# pca63519_-_Keyboard.net
KiCad netlist of a schematic drawn in Altium Designer
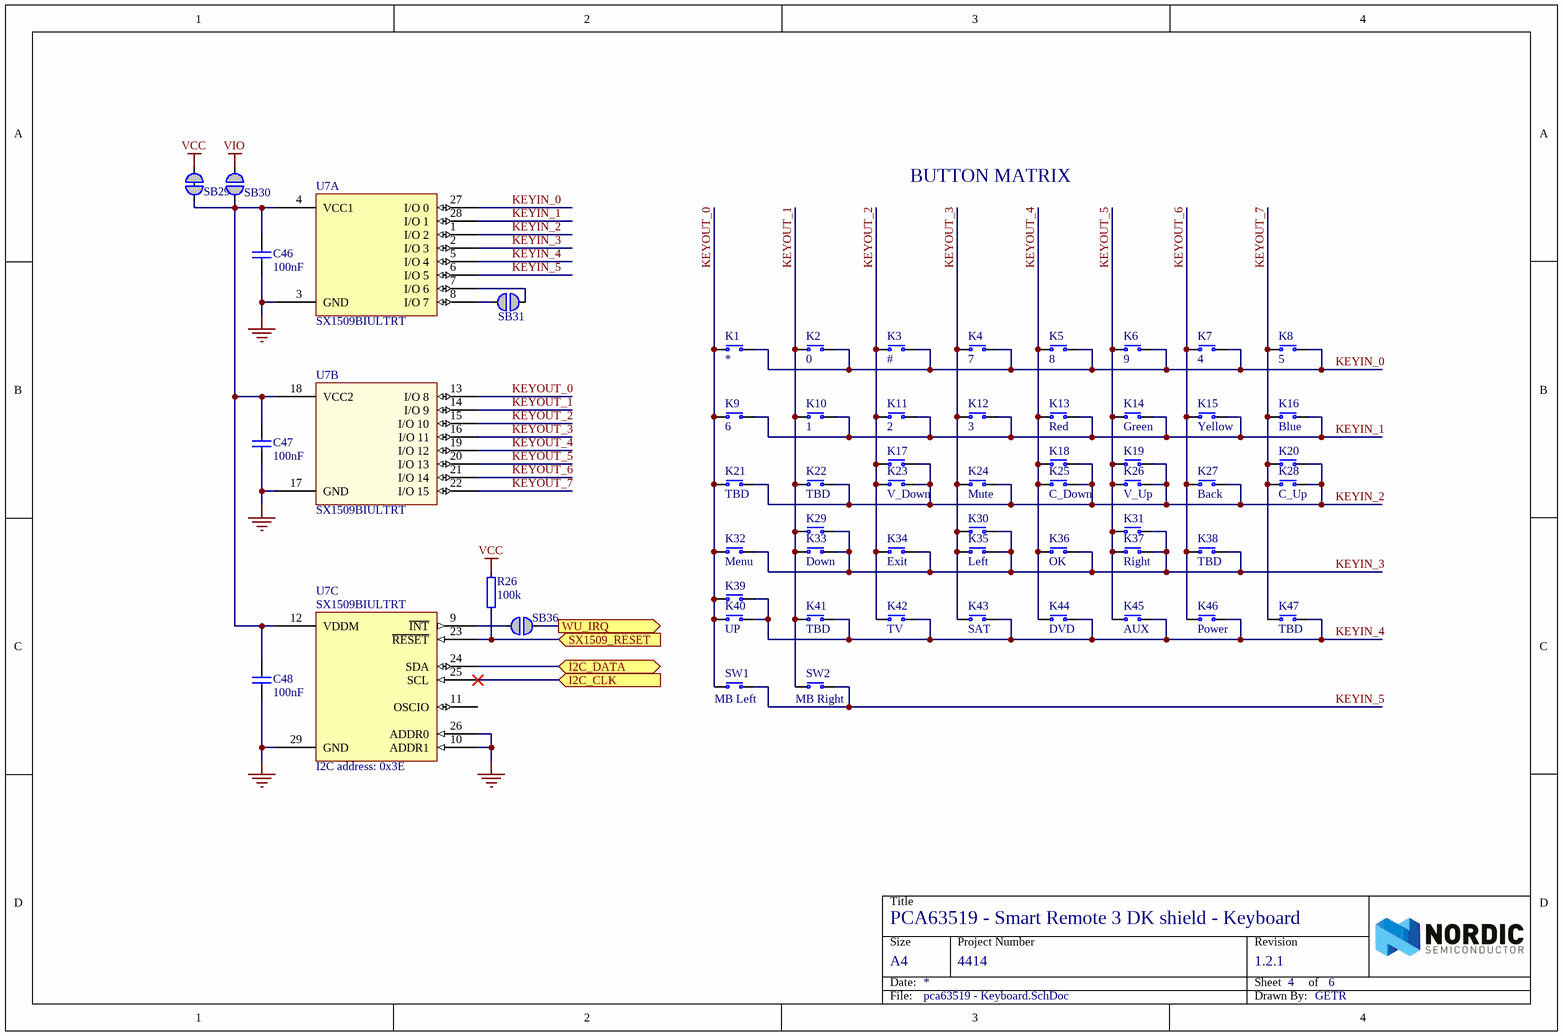
[diagram p0: pca63519 - Keyboard.SchDoc]

(export (version "E")
  (design (tool "Eeschema 10.0.6"))
  (components
    (comp (ref "C46")
      (value "100nF")
      (footprint "CAPC1005X04L")
      (description "Capacitor, X7R, ±10%")
      (fields (field (name "PART NUMBER") "C0402-100n") (field (name "PUBLISHER") "Nordic Semiconductor"))
      (libsource (lib "Nordic Passive DB") (part "CAP"))
    )
    (comp (ref "C47")
      (value "100nF")
      (footprint "CAPC1005X04L")
      (description "Capacitor, X7R, ±10%")
      (fields (field (name "PART NUMBER") "C0402-100n") (field (name "PUBLISHER") "Nordic Semiconductor"))
      (libsource (lib "Nordic Passive DB") (part "CAP"))
    )
    (comp (ref "C48")
      (value "100nF")
      (footprint "CAPC1005X04L")
      (description "Capacitor, X7R, ±10%")
      (fields (field (name "PART NUMBER") "C0402-100n") (field (name "PUBLISHER") "Nordic Semiconductor"))
      (libsource (lib "Nordic Passive DB") (part "CAP"))
    )
    (comp (ref "K1")
      (value "*")
      (footprint "PCB Switch")
      (description "Keyboard matrix switch")
      (fields (field (name "PART NUMBER") "KEY_SWITCH_SR3") (field (name "PUBLISHER") "Nordic Semiconductor"))
      (libsource (lib "Nordic Discrete DB") (part "SW-PCB"))
    )
    (comp (ref "K2")
      (value "0")
      (footprint "PCB Switch")
      (description "Keyboard matrix switch")
      (fields (field (name "PART NUMBER") "KEY_SWITCH_SR3") (field (name "PUBLISHER") "Nordic Semiconductor"))
      (libsource (lib "Nordic Discrete DB") (part "SW-PCB"))
    )
    (comp (ref "K3")
      (value "#")
      (footprint "PCB Switch")
      (description "Keyboard matrix switch")
      (fields (field (name "PART NUMBER") "KEY_SWITCH_SR3") (field (name "PUBLISHER") "Nordic Semiconductor"))
      (libsource (lib "Nordic Discrete DB") (part "SW-PCB"))
    )
    (comp (ref "K4")
      (value "7")
      (footprint "PCB Switch")
      (description "Keyboard matrix switch")
      (fields (field (name "PART NUMBER") "KEY_SWITCH_SR3") (field (name "PUBLISHER") "Nordic Semiconductor"))
      (libsource (lib "Nordic Discrete DB") (part "SW-PCB"))
    )
    (comp (ref "K5")
      (value "8")
      (footprint "PCB Switch")
      (description "Keyboard matrix switch")
      (fields (field (name "PART NUMBER") "KEY_SWITCH_SR3") (field (name "PUBLISHER") "Nordic Semiconductor"))
      (libsource (lib "Nordic Discrete DB") (part "SW-PCB"))
    )
    (comp (ref "K6")
      (value "9")
      (footprint "PCB Switch")
      (description "Keyboard matrix switch")
      (fields (field (name "PART NUMBER") "KEY_SWITCH_SR3") (field (name "PUBLISHER") "Nordic Semiconductor"))
      (libsource (lib "Nordic Discrete DB") (part "SW-PCB"))
    )
    (comp (ref "K7")
      (value "4")
      (footprint "PCB Switch")
      (description "Keyboard matrix switch")
      (fields (field (name "PART NUMBER") "KEY_SWITCH_SR3") (field (name "PUBLISHER") "Nordic Semiconductor"))
      (libsource (lib "Nordic Discrete DB") (part "SW-PCB"))
    )
    (comp (ref "K8")
      (value "5")
      (footprint "PCB Switch")
      (description "Keyboard matrix switch")
      (fields (field (name "PART NUMBER") "KEY_SWITCH_SR3") (field (name "PUBLISHER") "Nordic Semiconductor"))
      (libsource (lib "Nordic Discrete DB") (part "SW-PCB"))
    )
    (comp (ref "K9")
      (value "6")
      (footprint "PCB Switch")
      (description "Keyboard matrix switch")
      (fields (field (name "PART NUMBER") "KEY_SWITCH_SR3") (field (name "PUBLISHER") "Nordic Semiconductor"))
      (libsource (lib "Nordic Discrete DB") (part "SW-PCB"))
    )
    (comp (ref "K10")
      (value "1")
      (footprint "PCB Switch")
      (description "Keyboard matrix switch")
      (fields (field (name "PART NUMBER") "KEY_SWITCH_SR3") (field (name "PUBLISHER") "Nordic Semiconductor"))
      (libsource (lib "Nordic Discrete DB") (part "SW-PCB"))
    )
    (comp (ref "K11")
      (value "2")
      (footprint "PCB Switch")
      (description "Keyboard matrix switch")
      (fields (field (name "PART NUMBER") "KEY_SWITCH_SR3") (field (name "PUBLISHER") "Nordic Semiconductor"))
      (libsource (lib "Nordic Discrete DB") (part "SW-PCB"))
    )
    (comp (ref "K12")
      (value "3")
      (footprint "PCB Switch")
      (description "Keyboard matrix switch")
      (fields (field (name "PART NUMBER") "KEY_SWITCH_SR3") (field (name "PUBLISHER") "Nordic Semiconductor"))
      (libsource (lib "Nordic Discrete DB") (part "SW-PCB"))
    )
    (comp (ref "K13")
      (value "Red")
      (footprint "PCB Switch")
      (description "Keyboard matrix switch")
      (fields (field (name "PART NUMBER") "KEY_SWITCH_SR3") (field (name "PUBLISHER") "Nordic Semiconductor"))
      (libsource (lib "Nordic Discrete DB") (part "SW-PCB"))
    )
    (comp (ref "K14")
      (value "Green")
      (footprint "PCB Switch")
      (description "Keyboard matrix switch")
      (fields (field (name "PART NUMBER") "KEY_SWITCH_SR3") (field (name "PUBLISHER") "Nordic Semiconductor"))
      (libsource (lib "Nordic Discrete DB") (part "SW-PCB"))
    )
    (comp (ref "K15")
      (value "Yellow")
      (footprint "PCB Switch")
      (description "Keyboard matrix switch")
      (fields (field (name "PART NUMBER") "KEY_SWITCH_SR3") (field (name "PUBLISHER") "Nordic Semiconductor"))
      (libsource (lib "Nordic Discrete DB") (part "SW-PCB"))
    )
    (comp (ref "K16")
      (value "Blue")
      (footprint "PCB Switch")
      (description "Keyboard matrix switch")
      (fields (field (name "PART NUMBER") "KEY_SWITCH_SR3") (field (name "PUBLISHER") "Nordic Semiconductor"))
      (libsource (lib "Nordic Discrete DB") (part "SW-PCB"))
    )
    (comp (ref "K17")
      (value "PCB SW")
      (footprint "PCB Switch")
      (description "Keyboard matrix switch")
      (fields (field (name "PART NUMBER") "KEY_SWITCH_SR3") (field (name "PUBLISHER") "Nordic Semiconductor"))
      (libsource (lib "Nordic Discrete DB") (part "SW-PCB"))
    )
    (comp (ref "K18")
      (value "PCB SW")
      (footprint "PCB Switch")
      (description "Keyboard matrix switch")
      (fields (field (name "PART NUMBER") "KEY_SWITCH_SR3") (field (name "PUBLISHER") "Nordic Semiconductor"))
      (libsource (lib "Nordic Discrete DB") (part "SW-PCB"))
    )
    (comp (ref "K19")
      (value "PCB SW")
      (footprint "PCB Switch")
      (description "Keyboard matrix switch")
      (fields (field (name "PART NUMBER") "KEY_SWITCH_SR3") (field (name "PUBLISHER") "Nordic Semiconductor"))
      (libsource (lib "Nordic Discrete DB") (part "SW-PCB"))
    )
    (comp (ref "K20")
      (value "PCB SW")
      (footprint "PCB Switch")
      (description "Keyboard matrix switch")
      (fields (field (name "PART NUMBER") "KEY_SWITCH_SR3") (field (name "PUBLISHER") "Nordic Semiconductor"))
      (libsource (lib "Nordic Discrete DB") (part "SW-PCB"))
    )
    (comp (ref "K21")
      (value "TBD")
      (footprint "PCB Switch")
      (description "Keyboard matrix switch")
      (fields (field (name "PART NUMBER") "KEY_SWITCH_SR3") (field (name "PUBLISHER") "Nordic Semiconductor"))
      (libsource (lib "Nordic Discrete DB") (part "SW-PCB"))
    )
    (comp (ref "K22")
      (value "TBD")
      (footprint "PCB Switch")
      (description "Keyboard matrix switch")
      (fields (field (name "PART NUMBER") "KEY_SWITCH_SR3") (field (name "PUBLISHER") "Nordic Semiconductor"))
      (libsource (lib "Nordic Discrete DB") (part "SW-PCB"))
    )
    (comp (ref "K23")
      (value "V_Down")
      (footprint "PCB Switch")
      (description "Keyboard matrix switch")
      (fields (field (name "PART NUMBER") "KEY_SWITCH_SR3") (field (name "PUBLISHER") "Nordic Semiconductor"))
      (libsource (lib "Nordic Discrete DB") (part "SW-PCB"))
    )
    (comp (ref "K24")
      (value "Mute")
      (footprint "PCB Switch")
      (description "Keyboard matrix switch")
      (fields (field (name "PART NUMBER") "KEY_SWITCH_SR3") (field (name "PUBLISHER") "Nordic Semiconductor"))
      (libsource (lib "Nordic Discrete DB") (part "SW-PCB"))
    )
    (comp (ref "K25")
      (value "C_Down")
      (footprint "PCB Switch")
      (description "Keyboard matrix switch")
      (fields (field (name "PART NUMBER") "KEY_SWITCH_SR3") (field (name "PUBLISHER") "Nordic Semiconductor"))
      (libsource (lib "Nordic Discrete DB") (part "SW-PCB"))
    )
    (comp (ref "K26")
      (value "V_Up")
      (footprint "PCB Switch")
      (description "Keyboard matrix switch")
      (fields (field (name "PART NUMBER") "KEY_SWITCH_SR3") (field (name "PUBLISHER") "Nordic Semiconductor"))
      (libsource (lib "Nordic Discrete DB") (part "SW-PCB"))
    )
    (comp (ref "K27")
      (value "Back")
      (footprint "PCB Switch")
      (description "Keyboard matrix switch")
      (fields (field (name "PART NUMBER") "KEY_SWITCH_SR3") (field (name "PUBLISHER") "Nordic Semiconductor"))
      (libsource (lib "Nordic Discrete DB") (part "SW-PCB"))
    )
    (comp (ref "K28")
      (value "C_Up")
      (footprint "PCB Switch")
      (description "Keyboard matrix switch")
      (fields (field (name "PART NUMBER") "KEY_SWITCH_SR3") (field (name "PUBLISHER") "Nordic Semiconductor"))
      (libsource (lib "Nordic Discrete DB") (part "SW-PCB"))
    )
    (comp (ref "K29")
      (value "PCB SW")
      (footprint "PCB Switch")
      (description "Keyboard matrix switch")
      (fields (field (name "PART NUMBER") "KEY_SWITCH_SR3") (field (name "PUBLISHER") "Nordic Semiconductor"))
      (libsource (lib "Nordic Discrete DB") (part "SW-PCB"))
    )
    (comp (ref "K30")
      (value "PCB SW")
      (footprint "PCB Switch")
      (description "Keyboard matrix switch")
      (fields (field (name "PART NUMBER") "KEY_SWITCH_SR3") (field (name "PUBLISHER") "Nordic Semiconductor"))
      (libsource (lib "Nordic Discrete DB") (part "SW-PCB"))
    )
    (comp (ref "K31")
      (value "PCB SW")
      (footprint "PCB Switch")
      (description "Keyboard matrix switch")
      (fields (field (name "PART NUMBER") "KEY_SWITCH_SR3") (field (name "PUBLISHER") "Nordic Semiconductor"))
      (libsource (lib "Nordic Discrete DB") (part "SW-PCB"))
    )
    (comp (ref "K32")
      (value "Menu")
      (footprint "PCB Switch")
      (description "Keyboard matrix switch")
      (fields (field (name "PART NUMBER") "KEY_SWITCH_SR3") (field (name "PUBLISHER") "Nordic Semiconductor"))
      (libsource (lib "Nordic Discrete DB") (part "SW-PCB"))
    )
    (comp (ref "K33")
      (value "Down")
      (footprint "PCB Switch")
      (description "Keyboard matrix switch")
      (fields (field (name "PART NUMBER") "KEY_SWITCH_SR3") (field (name "PUBLISHER") "Nordic Semiconductor"))
      (libsource (lib "Nordic Discrete DB") (part "SW-PCB"))
    )
    (comp (ref "K34")
      (value "Exit")
      (footprint "PCB Switch")
      (description "Keyboard matrix switch")
      (fields (field (name "PART NUMBER") "KEY_SWITCH_SR3") (field (name "PUBLISHER") "Nordic Semiconductor"))
      (libsource (lib "Nordic Discrete DB") (part "SW-PCB"))
    )
    (comp (ref "K35")
      (value "Left")
      (footprint "PCB Switch")
      (description "Keyboard matrix switch")
      (fields (field (name "PART NUMBER") "KEY_SWITCH_SR3") (field (name "PUBLISHER") "Nordic Semiconductor"))
      (libsource (lib "Nordic Discrete DB") (part "SW-PCB"))
    )
    (comp (ref "K36")
      (value "OK")
      (footprint "PCB Switch")
      (description "Keyboard matrix switch")
      (fields (field (name "PART NUMBER") "KEY_SWITCH_SR3") (field (name "PUBLISHER") "Nordic Semiconductor"))
      (libsource (lib "Nordic Discrete DB") (part "SW-PCB"))
    )
    (comp (ref "K37")
      (value "Right")
      (footprint "PCB Switch")
      (description "Keyboard matrix switch")
      (fields (field (name "PART NUMBER") "KEY_SWITCH_SR3") (field (name "PUBLISHER") "Nordic Semiconductor"))
      (libsource (lib "Nordic Discrete DB") (part "SW-PCB"))
    )
    (comp (ref "K38")
      (value "TBD")
      (footprint "PCB Switch")
      (description "Keyboard matrix switch")
      (fields (field (name "PART NUMBER") "KEY_SWITCH_SR3") (field (name "PUBLISHER") "Nordic Semiconductor"))
      (libsource (lib "Nordic Discrete DB") (part "SW-PCB"))
    )
    (comp (ref "K39")
      (value "PCB SW")
      (footprint "PCB Switch")
      (description "Keyboard matrix switch")
      (fields (field (name "PART NUMBER") "KEY_SWITCH_SR3") (field (name "PUBLISHER") "Nordic Semiconductor"))
      (libsource (lib "Nordic Discrete DB") (part "SW-PCB"))
    )
    (comp (ref "K40")
      (value "UP")
      (footprint "PCB Switch")
      (description "Keyboard matrix switch")
      (fields (field (name "PART NUMBER") "KEY_SWITCH_SR3") (field (name "PUBLISHER") "Nordic Semiconductor"))
      (libsource (lib "Nordic Discrete DB") (part "SW-PCB"))
    )
    (comp (ref "K41")
      (value "TBD")
      (footprint "PCB Switch")
      (description "Keyboard matrix switch")
      (fields (field (name "PART NUMBER") "KEY_SWITCH_SR3") (field (name "PUBLISHER") "Nordic Semiconductor"))
      (libsource (lib "Nordic Discrete DB") (part "SW-PCB"))
    )
    (comp (ref "K42")
      (value "TV")
      (footprint "PCB Switch")
      (description "Keyboard matrix switch")
      (fields (field (name "PART NUMBER") "KEY_SWITCH_SR3") (field (name "PUBLISHER") "Nordic Semiconductor"))
      (libsource (lib "Nordic Discrete DB") (part "SW-PCB"))
    )
    (comp (ref "K43")
      (value "SAT")
      (footprint "PCB Switch")
      (description "Keyboard matrix switch")
      (fields (field (name "PART NUMBER") "KEY_SWITCH_SR3") (field (name "PUBLISHER") "Nordic Semiconductor"))
      (libsource (lib "Nordic Discrete DB") (part "SW-PCB"))
    )
    (comp (ref "K44")
      (value "DVD")
      (footprint "PCB Switch")
      (description "Keyboard matrix switch")
      (fields (field (name "PART NUMBER") "KEY_SWITCH_SR3") (field (name "PUBLISHER") "Nordic Semiconductor"))
      (libsource (lib "Nordic Discrete DB") (part "SW-PCB"))
    )
    (comp (ref "K45")
      (value "AUX")
      (footprint "PCB Switch")
      (description "Keyboard matrix switch")
      (fields (field (name "PART NUMBER") "KEY_SWITCH_SR3") (field (name "PUBLISHER") "Nordic Semiconductor"))
      (libsource (lib "Nordic Discrete DB") (part "SW-PCB"))
    )
    (comp (ref "K46")
      (value "Power")
      (footprint "PCB Switch")
      (description "Keyboard matrix switch")
      (fields (field (name "PART NUMBER") "KEY_SWITCH_SR3") (field (name "PUBLISHER") "Nordic Semiconductor"))
      (libsource (lib "Nordic Discrete DB") (part "SW-PCB"))
    )
    (comp (ref "K47")
      (value "TBD")
      (footprint "PCB Switch")
      (description "Keyboard matrix switch")
      (fields (field (name "PART NUMBER") "KEY_SWITCH_SR3") (field (name "PUBLISHER") "Nordic Semiconductor"))
      (libsource (lib "Nordic Discrete DB") (part "SW-PCB"))
    )
    (comp (ref "R26")
      (value "100k")
      (footprint "RESC1005X04L")
      (description "Resistor, ±1%, 0.063W")
      (fields (field (name "PART NUMBER") "R0402-100k") (field (name "PUBLISHER") "Nordic Semiconductor"))
      (libsource (lib "Nordic Passive DB") (part "RES_1"))
    )
    (comp (ref "SB29")
      (value "Solderbridge")
      (footprint "Solderbridge_SHORTED_0.4")
      (description "Shorted Solderbridge")
      (fields
        (field (name "PART NUMBER") "Solderbridge Shorted 0.4mm")
        (field (name "PUBLISHER") "Nordic Semiconductor")
      )
      (libsource (lib "Nordic Passive DB") (part "SOLDERBRIDGE_SHORTED"))
    )
    (comp (ref "SB30")
      (value "Solderbridge")
      (footprint "Solderbridge_0.4")
      (fields
        (field (name "PART NUMBER") "Solderbridge 0.4mm")
        (field (name "PUBLISHER") "Nordic Semiconductor")
      )
      (libsource (lib "Nordic Passive DB") (part "SOLDERBRIDGE"))
    )
    (comp (ref "SB31")
      (value "Solderbridge")
      (footprint "Solderbridge_0.4")
      (fields
        (field (name "PART NUMBER") "Solderbridge 0.4mm")
        (field (name "PUBLISHER") "Nordic Semiconductor")
      )
      (libsource (lib "Nordic Passive DB") (part "SOLDERBRIDGE"))
    )
    (comp (ref "SB36")
      (value "Solderbridge")
      (footprint "Solderbridge_0.4")
      (fields
        (field (name "PART NUMBER") "Solderbridge 0.4mm")
        (field (name "PUBLISHER") "Nordic Semiconductor")
      )
      (libsource (lib "Nordic Passive DB") (part "SOLDERBRIDGE"))
    )
    (comp (ref "SW1")
      (value "MB Left")
      (footprint "ALPS_SKHUxxx010_WO_GND")
      (description "ALPS - SKHUALE010 - Tactile Switch, SPNO, SMD, 6.5x6.2x2.5mm")
      (fields
        (field (name "PART NUMBER") "ALPS_SKHUALE010")
        (field (name "MANUFACTURER") "Alps")
        (field (name "PUBLISHER") "Nordic Semiconductor")
      )
      (libsource (lib "Nordic Discrete DB") (part "SW-PB"))
    )
    (comp (ref "SW2")
      (value "MB Right")
      (footprint "ALPS_SKHUxxx010_WO_GND")
      (description "ALPS - SKHUALE010 - Tactile Switch, SPNO, SMD, 6.5x6.2x2.5mm")
      (fields
        (field (name "PART NUMBER") "ALPS_SKHUALE010")
        (field (name "MANUFACTURER") "Alps")
        (field (name "PUBLISHER") "Nordic Semiconductor")
      )
      (libsource (lib "Nordic Discrete DB") (part "SW-PB"))
    )
    (comp (ref "U7")
      (value "SX1509BIULTRT")
      (footprint "QFN40P400X400X60_HS-29N")
      (description "IC GPIO EXPANDER I2C 16CH 28QFN")
      (fields
        (field (name "MANUFACTURER") "Semtech Corporation")
        (field (name "PUBLISHER") "Nordic Semiconductor")
      )
      (libsource (lib "Nordic Active DB") (part "SX1509"))
    )
  )
  (nets
    (net (code "1") (name "/I2C_CLK") (class "Default")
      (node (ref "U7") (pin "25") (pinfunction "SCL_25") (pintype "input+no_connect"))
    )
    (net (code "2") (name "/I2C_DATA") (class "Default")
      (node (ref "U7") (pin "24") (pinfunction "SDA_24") (pintype "bidirectional"))
    )
    (net (code "3") (name "/KEYIN_0") (class "Default")
      (node (ref "K1") (pin "1") (pinfunction "N.O_1") (pintype "passive"))
      (node (ref "K2") (pin "1") (pinfunction "N.O_1") (pintype "passive"))
      (node (ref "K3") (pin "1") (pinfunction "N.O_1") (pintype "passive"))
      (node (ref "K4") (pin "1") (pinfunction "N.O_1") (pintype "passive"))
      (node (ref "K5") (pin "1") (pinfunction "N.O_1") (pintype "passive"))
      (node (ref "K6") (pin "1") (pinfunction "N.O_1") (pintype "passive"))
      (node (ref "K7") (pin "1") (pinfunction "N.O_1") (pintype "passive"))
      (node (ref "K8") (pin "1") (pinfunction "N.O_1") (pintype "passive"))
      (node (ref "U7") (pin "27") (pinfunction "I/O_0_27") (pintype "bidirectional"))
    )
    (net (code "4") (name "/KEYIN_1") (class "Default")
      (node (ref "K10") (pin "1") (pinfunction "N.O_1") (pintype "passive"))
      (node (ref "K11") (pin "1") (pinfunction "N.O_1") (pintype "passive"))
      (node (ref "K12") (pin "1") (pinfunction "N.O_1") (pintype "passive"))
      (node (ref "K13") (pin "1") (pinfunction "N.O_1") (pintype "passive"))
      (node (ref "K14") (pin "1") (pinfunction "N.O_1") (pintype "passive"))
      (node (ref "K15") (pin "1") (pinfunction "N.O_1") (pintype "passive"))
      (node (ref "K16") (pin "1") (pinfunction "N.O_1") (pintype "passive"))
      (node (ref "K9") (pin "1") (pinfunction "N.O_1") (pintype "passive"))
      (node (ref "U7") (pin "28") (pinfunction "I/O_1_28") (pintype "bidirectional"))
    )
    (net (code "5") (name "/KEYIN_2") (class "Default")
      (node (ref "K17") (pin "1") (pinfunction "N.O_1") (pintype "passive"))
      (node (ref "K18") (pin "1") (pinfunction "N.O_1") (pintype "passive"))
      (node (ref "K19") (pin "1") (pinfunction "N.O_1") (pintype "passive"))
      (node (ref "K20") (pin "1") (pinfunction "N.O_1") (pintype "passive"))
      (node (ref "K21") (pin "1") (pinfunction "N.O_1") (pintype "passive"))
      (node (ref "K22") (pin "1") (pinfunction "N.O_1") (pintype "passive"))
      (node (ref "K23") (pin "1") (pinfunction "N.O_1") (pintype "passive"))
      (node (ref "K24") (pin "1") (pinfunction "N.O_1") (pintype "passive"))
      (node (ref "K25") (pin "1") (pinfunction "N.O_1") (pintype "passive"))
      (node (ref "K26") (pin "1") (pinfunction "N.O_1") (pintype "passive"))
      (node (ref "K27") (pin "1") (pinfunction "N.O_1") (pintype "passive"))
      (node (ref "K28") (pin "1") (pinfunction "N.O_1") (pintype "passive"))
      (node (ref "U7") (pin "1") (pinfunction "I/O_2_1") (pintype "bidirectional"))
    )
    (net (code "6") (name "/KEYIN_3") (class "Default")
      (node (ref "K29") (pin "1") (pinfunction "N.O_1") (pintype "passive"))
      (node (ref "K30") (pin "1") (pinfunction "N.O_1") (pintype "passive"))
      (node (ref "K31") (pin "1") (pinfunction "N.O_1") (pintype "passive"))
      (node (ref "K32") (pin "1") (pinfunction "N.O_1") (pintype "passive"))
      (node (ref "K33") (pin "1") (pinfunction "N.O_1") (pintype "passive"))
      (node (ref "K34") (pin "1") (pinfunction "N.O_1") (pintype "passive"))
      (node (ref "K35") (pin "1") (pinfunction "N.O_1") (pintype "passive"))
      (node (ref "K36") (pin "1") (pinfunction "N.O_1") (pintype "passive"))
      (node (ref "K37") (pin "1") (pinfunction "N.O_1") (pintype "passive"))
      (node (ref "K38") (pin "1") (pinfunction "N.O_1") (pintype "passive"))
      (node (ref "U7") (pin "2") (pinfunction "I/O_3_2") (pintype "bidirectional"))
    )
    (net (code "7") (name "/KEYIN_4") (class "Default")
      (node (ref "K39") (pin "1") (pinfunction "N.O_1") (pintype "passive"))
      (node (ref "K40") (pin "1") (pinfunction "N.O_1") (pintype "passive"))
      (node (ref "K41") (pin "1") (pinfunction "N.O_1") (pintype "passive"))
      (node (ref "K42") (pin "1") (pinfunction "N.O_1") (pintype "passive"))
      (node (ref "K43") (pin "1") (pinfunction "N.O_1") (pintype "passive"))
      (node (ref "K44") (pin "1") (pinfunction "N.O_1") (pintype "passive"))
      (node (ref "K45") (pin "1") (pinfunction "N.O_1") (pintype "passive"))
      (node (ref "K46") (pin "1") (pinfunction "N.O_1") (pintype "passive"))
      (node (ref "K47") (pin "1") (pinfunction "N.O_1") (pintype "passive"))
      (node (ref "U7") (pin "5") (pinfunction "I/O_4_5") (pintype "bidirectional"))
    )
    (net (code "8") (name "/KEYIN_5") (class "Default")
      (node (ref "SW1") (pin "1") (pinfunction "N.O_1") (pintype "passive"))
      (node (ref "SW2") (pin "1") (pinfunction "N.O_1") (pintype "passive"))
      (node (ref "U7") (pin "6") (pinfunction "I/O_5_6") (pintype "bidirectional"))
    )
    (net (code "9") (name "/KEYOUT_0") (class "Default")
      (node (ref "K1") (pin "2") (pinfunction "COM_2") (pintype "passive"))
      (node (ref "K21") (pin "2") (pinfunction "COM_2") (pintype "passive"))
      (node (ref "K32") (pin "2") (pinfunction "COM_2") (pintype "passive"))
      (node (ref "K39") (pin "2") (pinfunction "COM_2") (pintype "passive"))
      (node (ref "K40") (pin "2") (pinfunction "COM_2") (pintype "passive"))
      (node (ref "K9") (pin "2") (pinfunction "COM_2") (pintype "passive"))
      (node (ref "SW1") (pin "2") (pinfunction "COM_2") (pintype "passive"))
      (node (ref "U7") (pin "13") (pinfunction "I/O_8_13") (pintype "bidirectional"))
    )
    (net (code "10") (name "/KEYOUT_1") (class "Default")
      (node (ref "K10") (pin "2") (pinfunction "COM_2") (pintype "passive"))
      (node (ref "K2") (pin "2") (pinfunction "COM_2") (pintype "passive"))
      (node (ref "K22") (pin "2") (pinfunction "COM_2") (pintype "passive"))
      (node (ref "K29") (pin "2") (pinfunction "COM_2") (pintype "passive"))
      (node (ref "K33") (pin "2") (pinfunction "COM_2") (pintype "passive"))
      (node (ref "K41") (pin "2") (pinfunction "COM_2") (pintype "passive"))
      (node (ref "SW2") (pin "2") (pinfunction "COM_2") (pintype "passive"))
      (node (ref "U7") (pin "14") (pinfunction "I/O_9_14") (pintype "bidirectional"))
    )
    (net (code "11") (name "/KEYOUT_2") (class "Default")
      (node (ref "K11") (pin "2") (pinfunction "COM_2") (pintype "passive"))
      (node (ref "K17") (pin "2") (pinfunction "COM_2") (pintype "passive"))
      (node (ref "K23") (pin "2") (pinfunction "COM_2") (pintype "passive"))
      (node (ref "K3") (pin "2") (pinfunction "COM_2") (pintype "passive"))
      (node (ref "K34") (pin "2") (pinfunction "COM_2") (pintype "passive"))
      (node (ref "K42") (pin "2") (pinfunction "COM_2") (pintype "passive"))
      (node (ref "U7") (pin "15") (pinfunction "I/O_10_15") (pintype "bidirectional"))
    )
    (net (code "12") (name "/KEYOUT_3") (class "Default")
      (node (ref "K12") (pin "2") (pinfunction "COM_2") (pintype "passive"))
      (node (ref "K24") (pin "2") (pinfunction "COM_2") (pintype "passive"))
      (node (ref "K30") (pin "2") (pinfunction "COM_2") (pintype "passive"))
      (node (ref "K35") (pin "2") (pinfunction "COM_2") (pintype "passive"))
      (node (ref "K4") (pin "2") (pinfunction "COM_2") (pintype "passive"))
      (node (ref "K43") (pin "2") (pinfunction "COM_2") (pintype "passive"))
      (node (ref "U7") (pin "16") (pinfunction "I/O_11_16") (pintype "bidirectional"))
    )
    (net (code "13") (name "/KEYOUT_4") (class "Default")
      (node (ref "K13") (pin "2") (pinfunction "COM_2") (pintype "passive"))
      (node (ref "K18") (pin "2") (pinfunction "COM_2") (pintype "passive"))
      (node (ref "K25") (pin "2") (pinfunction "COM_2") (pintype "passive"))
      (node (ref "K36") (pin "2") (pinfunction "COM_2") (pintype "passive"))
      (node (ref "K44") (pin "2") (pinfunction "COM_2") (pintype "passive"))
      (node (ref "K5") (pin "2") (pinfunction "COM_2") (pintype "passive"))
      (node (ref "U7") (pin "19") (pinfunction "I/O_12_19") (pintype "bidirectional"))
    )
    (net (code "14") (name "/KEYOUT_5") (class "Default")
      (node (ref "K14") (pin "2") (pinfunction "COM_2") (pintype "passive"))
      (node (ref "K19") (pin "2") (pinfunction "COM_2") (pintype "passive"))
      (node (ref "K26") (pin "2") (pinfunction "COM_2") (pintype "passive"))
      (node (ref "K31") (pin "2") (pinfunction "COM_2") (pintype "passive"))
      (node (ref "K37") (pin "2") (pinfunction "COM_2") (pintype "passive"))
      (node (ref "K45") (pin "2") (pinfunction "COM_2") (pintype "passive"))
      (node (ref "K6") (pin "2") (pinfunction "COM_2") (pintype "passive"))
      (node (ref "U7") (pin "20") (pinfunction "I/O_13_20") (pintype "bidirectional"))
    )
    (net (code "15") (name "/KEYOUT_6") (class "Default")
      (node (ref "K15") (pin "2") (pinfunction "COM_2") (pintype "passive"))
      (node (ref "K27") (pin "2") (pinfunction "COM_2") (pintype "passive"))
      (node (ref "K38") (pin "2") (pinfunction "COM_2") (pintype "passive"))
      (node (ref "K46") (pin "2") (pinfunction "COM_2") (pintype "passive"))
      (node (ref "K7") (pin "2") (pinfunction "COM_2") (pintype "passive"))
      (node (ref "U7") (pin "21") (pinfunction "I/O_14_21") (pintype "bidirectional"))
    )
    (net (code "16") (name "/KEYOUT_7") (class "Default")
      (node (ref "K16") (pin "2") (pinfunction "COM_2") (pintype "passive"))
      (node (ref "K20") (pin "2") (pinfunction "COM_2") (pintype "passive"))
      (node (ref "K28") (pin "2") (pinfunction "COM_2") (pintype "passive"))
      (node (ref "K47") (pin "2") (pinfunction "COM_2") (pintype "passive"))
      (node (ref "K8") (pin "2") (pinfunction "COM_2") (pintype "passive"))
      (node (ref "U7") (pin "22") (pinfunction "I/O_15_22") (pintype "bidirectional"))
    )
    (net (code "17") (name "/SX1509_RESET") (class "Default")
      (node (ref "R26") (pin "1") (pinfunction "1_1") (pintype "passive"))
      (node (ref "U7") (pin "23") (pinfunction "~{RESET}_23") (pintype "input"))
    )
    (net (code "18") (name "/WU_IRQ") (class "Default")
      (node (ref "SB36") (pin "1") (pinfunction "0_1") (pintype "passive"))
    )
    (net (code "19") (name "GND") (class "Default")
      (node (ref "C46") (pin "1") (pinfunction "1_1") (pintype "passive"))
      (node (ref "C47") (pin "1") (pinfunction "1_1") (pintype "passive"))
      (node (ref "C48") (pin "1") (pinfunction "1_1") (pintype "passive"))
      (node (ref "U7") (pin "10") (pinfunction "ADDR1_10") (pintype "input"))
      (node (ref "U7") (pin "17") (pinfunction "GND_17") (pintype "power_in"))
      (node (ref "U7") (pin "26") (pinfunction "ADDR0_26") (pintype "input"))
      (node (ref "U7") (pin "29") (pinfunction "GND_29") (pintype "power_in"))
      (node (ref "U7") (pin "3") (pinfunction "GND_3") (pintype "power_in"))
    )
    (net (code "20") (name "Net-(SB29-1)") (class "Default")
      (node (ref "C46") (pin "2") (pinfunction "2_2") (pintype "passive"))
      (node (ref "C47") (pin "2") (pinfunction "2_2") (pintype "passive"))
      (node (ref "C48") (pin "2") (pinfunction "2_2") (pintype "passive"))
      (node (ref "SB29") (pin "2") (pinfunction "1_2") (pintype "passive"))
      (node (ref "SB30") (pin "2") (pinfunction "1_2") (pintype "passive"))
      (node (ref "U7") (pin "12") (pinfunction "VDDM_12") (pintype "power_in"))
      (node (ref "U7") (pin "18") (pinfunction "VCC2_18") (pintype "power_in"))
      (node (ref "U7") (pin "4") (pinfunction "VCC1_4") (pintype "power_in"))
    )
    (net (code "21") (name "Net-(SB31-0)") (class "Default")
      (node (ref "SB31") (pin "1") (pinfunction "0_1") (pintype "passive"))
      (node (ref "U7") (pin "8") (pinfunction "I/O_7_8") (pintype "bidirectional"))
    )
    (net (code "22") (name "Net-(SB31-1)") (class "Default")
      (node (ref "SB31") (pin "2") (pinfunction "1_2") (pintype "passive"))
      (node (ref "U7") (pin "7") (pinfunction "I/O_6_7") (pintype "bidirectional"))
    )
    (net (code "23") (name "Net-(SB36-1)") (class "Default")
      (node (ref "SB36") (pin "2") (pinfunction "1_2") (pintype "passive"))
      (node (ref "U7") (pin "9") (pinfunction "~{INT}_9") (pintype "output"))
    )
    (net (code "24") (name "VCC") (class "Default")
      (node (ref "R26") (pin "2") (pinfunction "2_2") (pintype "passive"))
      (node (ref "SB29") (pin "1") (pinfunction "0_1") (pintype "passive"))
    )
    (net (code "25") (name "VIO") (class "Default")
      (node (ref "SB30") (pin "1") (pinfunction "0_1") (pintype "passive"))
    )
    (net (code "26") (name "unconnected-(U7C-OSCIO-Pad11)") (class "Default")
      (node (ref "U7") (pin "11") (pinfunction "OSCIO_11") (pintype "bidirectional"))
    )
  )
)
